# StepperDriver.net
KiCad netlist of a schematic drawn in Altium Designer
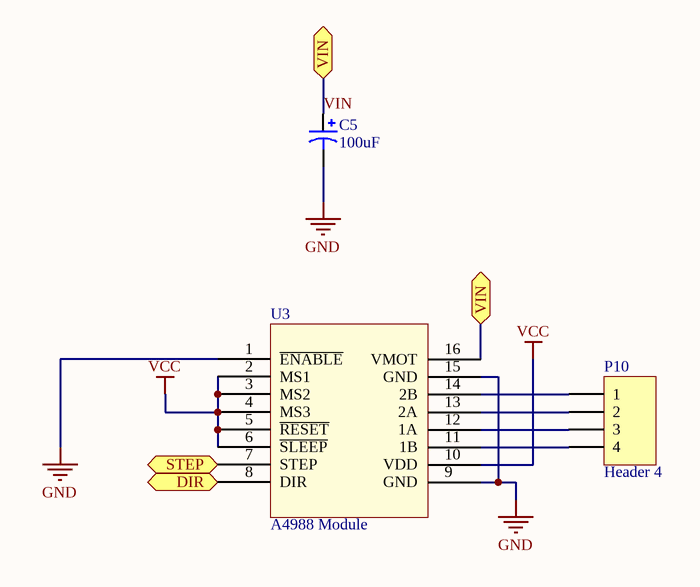
[diagram p0: StepperDriver.SchDoc]

(export (version "E")
  (design (tool "Eeschema 10.0.6"))
  (components
    (comp (ref "C5")
      (value "100uF")
      (footprint "Aluminum Electrolytic Short")
      (description "Electrolytic Cap")
      (fields
        (field (name "DIGI-KEY PART NO.") "493-2203-1-ND")
        (field (name "MANUFACTURER PART NO.") "UWT1V101MCL1GS")
      )
      (libsource (lib "polar cap") (part "Electrolytic Cap"))
    )
    (comp (ref "P10")
      (value "Header 4")
      (footprint "HDR1X4")
      (description "Header, 4-Pin")
      (fields (field (name "PUBLISHER") "Altium Limited"))
      (libsource (lib "Miscellaneous Connectors") (part "Header 4"))
    )
    (comp (ref "U3")
      (value "A4988 Module")
      (footprint "A4988 Header")
      (libsource (lib "Connectors") (part "A4988 Module"))
    )
  )
  (nets
    (net (code "1") (name "/DIR") (class "Default")
      (node (ref "U3") (pin "8") (pinfunction "DIR_8") (pintype "passive"))
    )
    (net (code "2") (name "/STEP") (class "Default")
      (node (ref "U3") (pin "7") (pinfunction "STEP_7") (pintype "passive"))
    )
    (net (code "3") (name "/VIN") (class "Default")
      (node (ref "C5") (pin "1") (pinfunction "1_1") (pintype "passive"))
      (node (ref "U3") (pin "16") (pinfunction "VMOT_16") (pintype "passive"))
    )
    (net (code "4") (name "GND") (class "Default")
      (node (ref "C5") (pin "2") (pinfunction "2_2") (pintype "passive"))
      (node (ref "U3") (pin "1") (pinfunction "~{ENABLE}_1") (pintype "passive"))
      (node (ref "U3") (pin "15") (pinfunction "GND_15") (pintype "passive"))
      (node (ref "U3") (pin "9") (pinfunction "GND_9") (pintype "passive"))
    )
    (net (code "5") (name "Net-(U3-1A)") (class "Default")
      (node (ref "P10") (pin "3") (pinfunction "3_3") (pintype "passive"))
      (node (ref "U3") (pin "12") (pinfunction "1A_12") (pintype "passive"))
    )
    (net (code "6") (name "Net-(U3-1B)") (class "Default")
      (node (ref "P10") (pin "4") (pinfunction "4_4") (pintype "passive"))
      (node (ref "U3") (pin "11") (pinfunction "1B_11") (pintype "passive"))
    )
    (net (code "7") (name "Net-(U3-2A)") (class "Default")
      (node (ref "P10") (pin "2") (pinfunction "2_2") (pintype "passive"))
      (node (ref "U3") (pin "13") (pinfunction "2A_13") (pintype "passive"))
    )
    (net (code "8") (name "Net-(U3-2B)") (class "Default")
      (node (ref "P10") (pin "1") (pinfunction "1_1") (pintype "passive"))
      (node (ref "U3") (pin "14") (pinfunction "2B_14") (pintype "passive"))
    )
    (net (code "9") (name "VCC") (class "Default")
      (node (ref "U3") (pin "10") (pinfunction "VDD_10") (pintype "passive"))
      (node (ref "U3") (pin "2") (pinfunction "MS1_2") (pintype "passive"))
      (node (ref "U3") (pin "3") (pinfunction "MS2_3") (pintype "passive"))
      (node (ref "U3") (pin "4") (pinfunction "MS3_4") (pintype "passive"))
      (node (ref "U3") (pin "5") (pinfunction "~{RESET}_5") (pintype "passive"))
      (node (ref "U3") (pin "6") (pinfunction "~{SLEEP}_6") (pintype "passive"))
    )
  )
)
